# stm32-d40.net
KiCad netlist of a schematic drawn in EAGLE
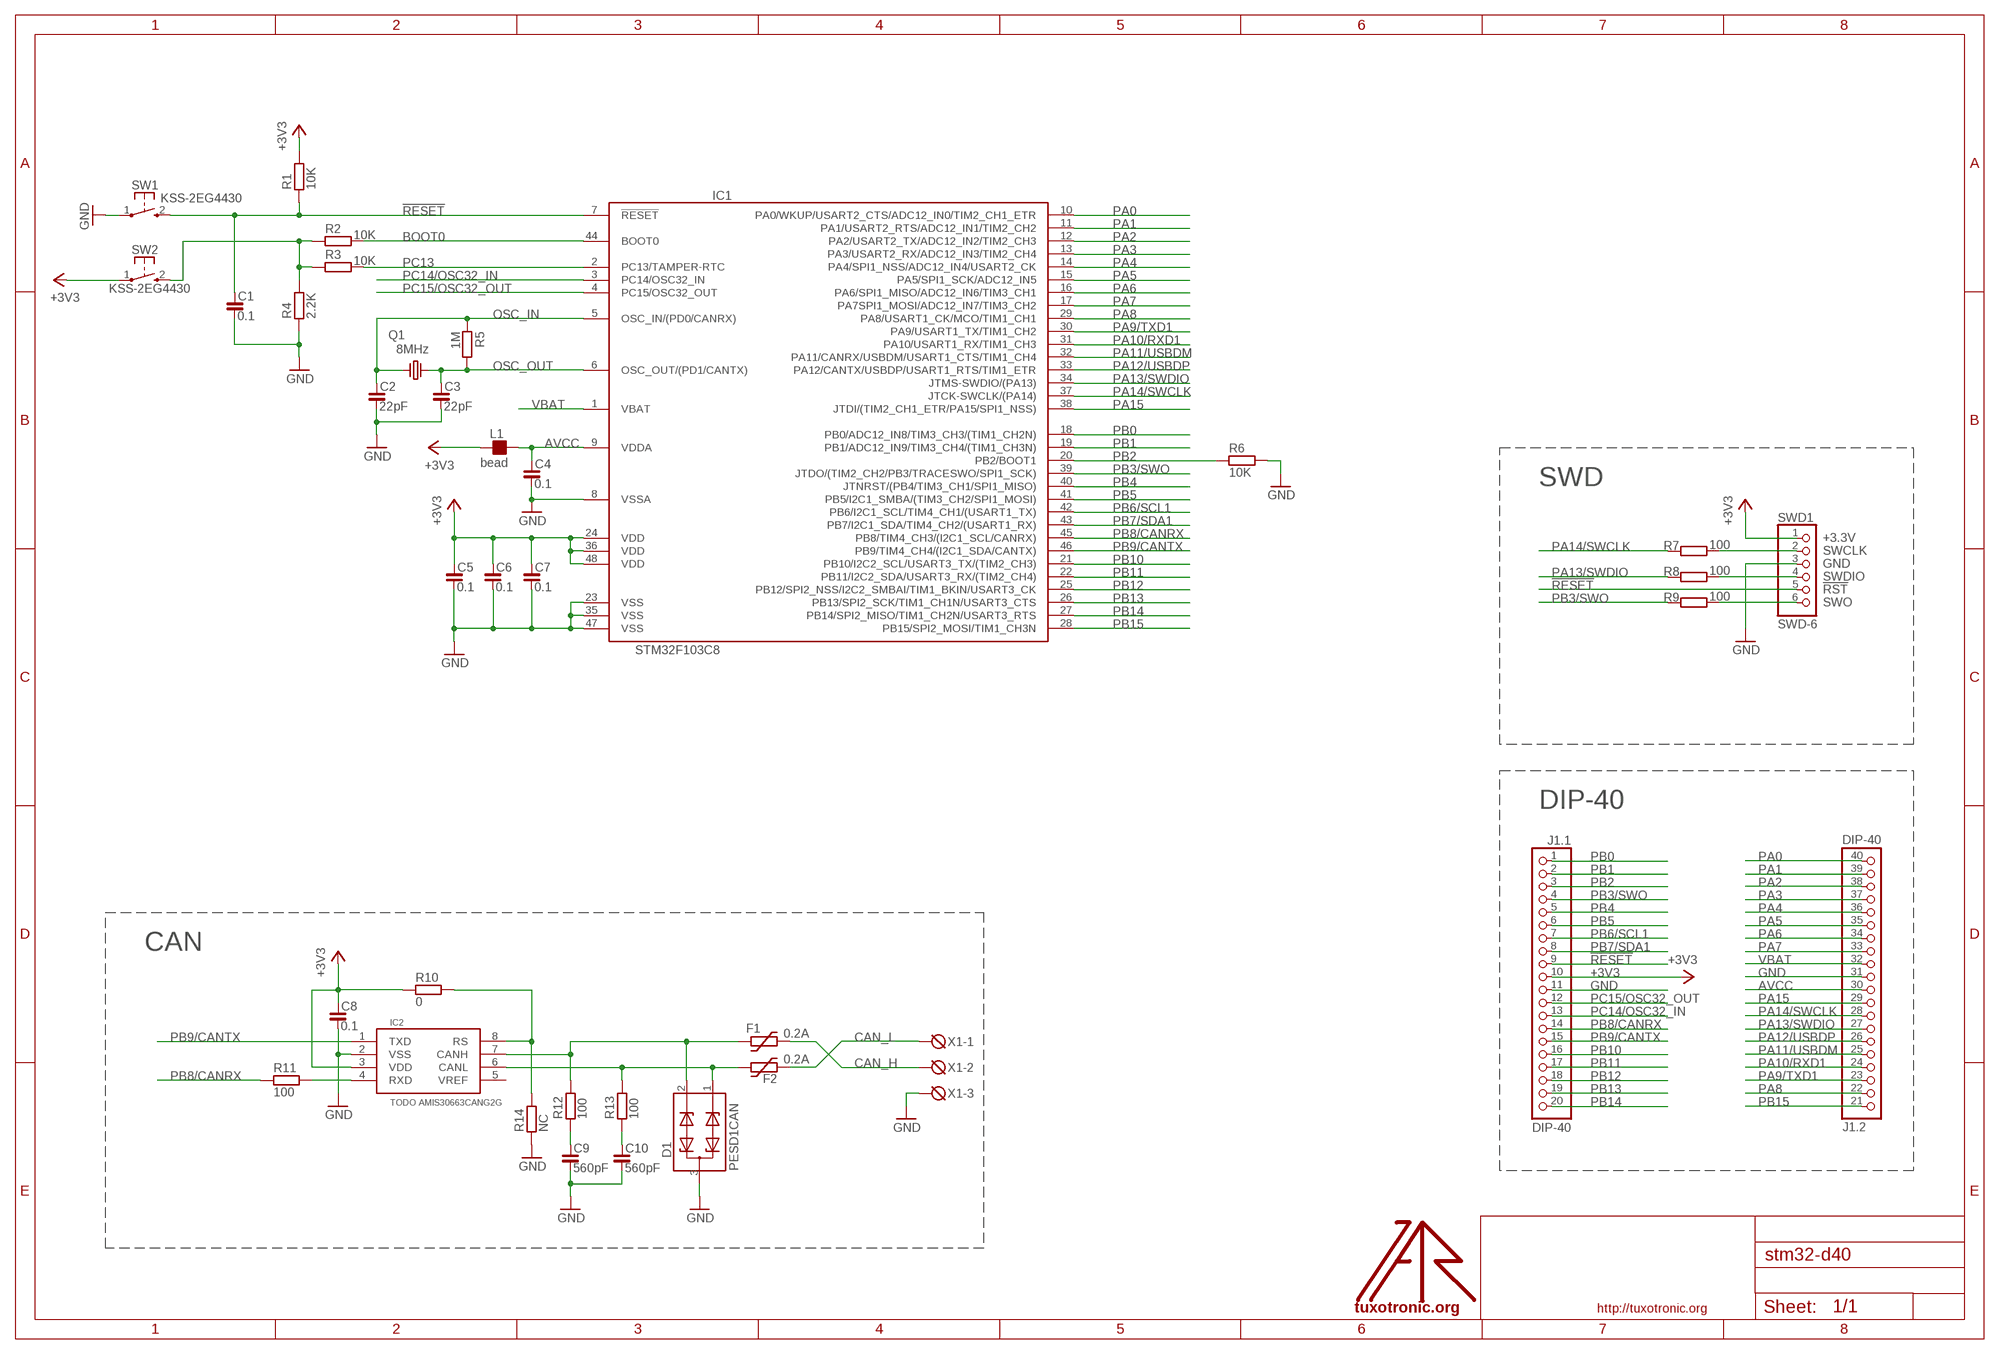
[diagram p0: schematic, sheet 1]

(export (version "E")
  (design (tool "Eeschema 10.0.6"))
  (components
    (comp (ref "C1")
      (value "0.1")
      (footprint "eagle-import:C0603")
      (libsource (lib "eagle-import") (part "C_0603"))
    )
    (comp (ref "C2")
      (value "22pF")
      (footprint "eagle-import:C0603")
      (libsource (lib "eagle-import") (part "C_0603"))
    )
    (comp (ref "C3")
      (value "22pF")
      (footprint "eagle-import:C0603")
      (libsource (lib "eagle-import") (part "C_0603"))
    )
    (comp (ref "C4")
      (value "0.1")
      (footprint "eagle-import:C0603")
      (libsource (lib "eagle-import") (part "C_0603"))
    )
    (comp (ref "C5")
      (value "0.1")
      (footprint "eagle-import:C0603")
      (libsource (lib "eagle-import") (part "C_0603"))
    )
    (comp (ref "C6")
      (value "0.1")
      (footprint "eagle-import:C0603")
      (libsource (lib "eagle-import") (part "C_0603"))
    )
    (comp (ref "C7")
      (value "0.1")
      (footprint "eagle-import:C0603")
      (libsource (lib "eagle-import") (part "C_0603"))
    )
    (comp (ref "C8")
      (value "0.1")
      (footprint "eagle-import:C0603")
      (libsource (lib "eagle-import") (part "C_0603"))
    )
    (comp (ref "C9")
      (value "560pF")
      (footprint "eagle-import:C0603")
      (libsource (lib "eagle-import") (part "C_0603"))
    )
    (comp (ref "C10")
      (value "560pF")
      (footprint "eagle-import:C0603")
      (libsource (lib "eagle-import") (part "C_0603"))
    )
    (comp (ref "D1")
      (value "PESD1CAN")
      (footprint "eagle-import:SOT23")
      (libsource (lib "eagle-import") (part "PESD1CAN"))
    )
    (comp (ref "F1")
      (value "0.2A")
      (footprint "eagle-import:1206L")
      (libsource (lib "eagle-import") (part "1206L"))
    )
    (comp (ref "F2")
      (value "0.2A")
      (footprint "eagle-import:1206L")
      (libsource (lib "eagle-import") (part "1206L"))
    )
    (comp (ref "IC1")
      (value "STM32F103C8")
      (footprint "eagle-import:LQFP48")
      (libsource (lib "eagle-import") (part "STM32F103C8"))
    )
    (comp (ref "IC2")
      (value "TODO AMIS30663CANG2G")
      (footprint "eagle-import:SO08")
      (libsource (lib "eagle-import") (part "SN65HVD230"))
    )
    (comp (ref "J1")
      (value "DIP-40")
      (footprint "eagle-import:DIP-40")
      (libsource (lib "eagle-import") (part "DIP-40"))
    )
    (comp (ref "L1")
      (value "bead")
      (footprint "eagle-import:L0603")
      (libsource (lib "eagle-import") (part "FB_0603"))
    )
    (comp (ref "Q1")
      (value "8MHz")
      (footprint "eagle-import:HC49_S")
      (libsource (lib "eagle-import") (part "CRYSTAL-HC49S"))
    )
    (comp (ref "R1")
      (value "10K")
      (footprint "eagle-import:R0603")
      (libsource (lib "eagle-import") (part "R_0603"))
    )
    (comp (ref "R2")
      (value "10K")
      (footprint "eagle-import:R0603")
      (libsource (lib "eagle-import") (part "R_0603"))
    )
    (comp (ref "R3")
      (value "10K")
      (footprint "eagle-import:R0603")
      (libsource (lib "eagle-import") (part "R_0603"))
    )
    (comp (ref "R4")
      (value "2.2K")
      (footprint "eagle-import:R0603")
      (libsource (lib "eagle-import") (part "R_0603"))
    )
    (comp (ref "R5")
      (value "1M")
      (footprint "eagle-import:R0603")
      (libsource (lib "eagle-import") (part "R_0603"))
    )
    (comp (ref "R6")
      (value "10K")
      (footprint "eagle-import:R0603")
      (libsource (lib "eagle-import") (part "R_0603"))
    )
    (comp (ref "R7")
      (value "100")
      (footprint "eagle-import:R0603")
      (libsource (lib "eagle-import") (part "R_0603"))
    )
    (comp (ref "R8")
      (value "100")
      (footprint "eagle-import:R0603")
      (libsource (lib "eagle-import") (part "R_0603"))
    )
    (comp (ref "R9")
      (value "100")
      (footprint "eagle-import:R0603")
      (libsource (lib "eagle-import") (part "R_0603"))
    )
    (comp (ref "R10")
      (value "0")
      (footprint "eagle-import:R0603")
      (libsource (lib "eagle-import") (part "R_0603"))
    )
    (comp (ref "R11")
      (value "100")
      (footprint "eagle-import:R0603")
      (libsource (lib "eagle-import") (part "R_0603"))
    )
    (comp (ref "R12")
      (value "100")
      (footprint "eagle-import:R0603")
      (libsource (lib "eagle-import") (part "R_0603"))
    )
    (comp (ref "R13")
      (value "100")
      (footprint "eagle-import:R0603")
      (libsource (lib "eagle-import") (part "R_0603"))
    )
    (comp (ref "R14")
      (value "NC")
      (footprint "eagle-import:R0603")
      (libsource (lib "eagle-import") (part "R_0603"))
    )
    (comp (ref "SW1")
      (value "KSS-2EG4430")
      (footprint "eagle-import:KSS-2EG4430")
      (libsource (lib "eagle-import") (part "KSS-2EG4430"))
    )
    (comp (ref "SW2")
      (value "KSS-2EG4430")
      (footprint "eagle-import:KSS-2EG4430")
      (libsource (lib "eagle-import") (part "KSS-2EG4430"))
    )
    (comp (ref "SWD1")
      (value "SWD-6")
      (footprint "eagle-import:JTAG6PIN")
      (libsource (lib "eagle-import") (part "SWD-6"))
    )
    (comp (ref "U$")
      (value "LOGO")
      (footprint "eagle-import:TT_LOGO")
      (libsource (lib "eagle-import") (part "LOGO"))
    )
    (comp (ref "X1")
      (value "DG3XX-03-3.5")
      (footprint "eagle-import:DG350-3.5-03P")
      (libsource (lib "eagle-import") (part "DG3XX-03-3.5"))
    )
  )
  (nets
    (net (code "1") (name "+3V3") (class "Default")
      (node (ref "C5") (pin "1") (pinfunction "1_1") (pintype "passive"))
      (node (ref "C6") (pin "1") (pinfunction "1_1") (pintype "passive"))
      (node (ref "C7") (pin "1") (pinfunction "1_1") (pintype "passive"))
      (node (ref "C8") (pin "1") (pinfunction "1_1") (pintype "passive"))
      (node (ref "IC1") (pin "24") (pinfunction "VDD_24") (pintype "power_in"))
      (node (ref "IC1") (pin "36") (pinfunction "VDD_36") (pintype "power_in"))
      (node (ref "IC1") (pin "48") (pinfunction "VDD_48") (pintype "power_in"))
      (node (ref "IC2") (pin "3") (pinfunction "VDD_3") (pintype "power_in"))
      (node (ref "J1") (pin "10") (pinfunction "10_10") (pintype "passive"))
      (node (ref "L1") (pin "1") (pinfunction "1_1") (pintype "passive"))
      (node (ref "R1") (pin "2") (pinfunction "2_2") (pintype "passive"))
      (node (ref "R10") (pin "1") (pinfunction "1_1") (pintype "passive"))
      (node (ref "SW2") (pin "1") (pinfunction "P_1") (pintype "passive"))
      (node (ref "SWD1") (pin "1") (pinfunction "1_1") (pintype "passive"))
    )
    (net (code "2") (name "/AVCC") (class "Default")
      (node (ref "C4") (pin "1") (pinfunction "1_1") (pintype "passive"))
      (node (ref "IC1") (pin "9") (pinfunction "VDDA_9") (pintype "power_in"))
      (node (ref "J1") (pin "30") (pinfunction "10_30") (pintype "passive"))
      (node (ref "L1") (pin "2") (pinfunction "2_2") (pintype "passive"))
    )
    (net (code "3") (name "/BOOT0") (class "Default")
      (node (ref "IC1") (pin "44") (pinfunction "BOOT0_44") (pintype "input"))
      (node (ref "R2") (pin "2") (pinfunction "2_2") (pintype "passive"))
    )
    (net (code "4") (name "/CAN_H") (class "Default")
      (node (ref "F1") (pin "P$2") (pinfunction "2_P$2") (pintype "passive"))
      (node (ref "X1") (pin "2") (pinfunction "KL_2") (pintype "passive"))
    )
    (net (code "5") (name "/CAN_L") (class "Default")
      (node (ref "F2") (pin "P$2") (pinfunction "2_P$2") (pintype "passive"))
      (node (ref "X1") (pin "1") (pinfunction "KL_1") (pintype "passive"))
    )
    (net (code "6") (name "/OSC_IN") (class "Default")
      (node (ref "C2") (pin "1") (pinfunction "1_1") (pintype "passive"))
      (node (ref "IC1") (pin "5") (pinfunction "OSC_IN/(PD0/CANRX)_5") (pintype "input"))
      (node (ref "Q1") (pin "1") (pinfunction "1_1") (pintype "passive"))
      (node (ref "R5") (pin "1") (pinfunction "1_1") (pintype "passive"))
    )
    (net (code "7") (name "/OSC_OUT") (class "Default")
      (node (ref "C3") (pin "1") (pinfunction "1_1") (pintype "passive"))
      (node (ref "IC1") (pin "6") (pinfunction "OSC_OUT/(PD1/CANTX)_6") (pintype "output"))
      (node (ref "Q1") (pin "2") (pinfunction "2_2") (pintype "passive"))
      (node (ref "R5") (pin "2") (pinfunction "2_2") (pintype "passive"))
    )
    (net (code "8") (name "/PA0") (class "Default")
      (node (ref "IC1") (pin "10") (pinfunction "PA0/WKUP/USART2_CTS/ADC12_IN0/TIM2_CH1_ETR_10") (pintype "bidirectional"))
      (node (ref "J1") (pin "40") (pinfunction "20_40") (pintype "passive"))
    )
    (net (code "9") (name "/PA1") (class "Default")
      (node (ref "IC1") (pin "11") (pinfunction "PA1/USART2_RTS/ADC12_IN1/TIM2_CH2_11") (pintype "bidirectional"))
      (node (ref "J1") (pin "39") (pinfunction "19_39") (pintype "passive"))
    )
    (net (code "10") (name "/PA2") (class "Default")
      (node (ref "IC1") (pin "12") (pinfunction "PA2/USART2_TX/ADC12_IN2/TIM2_CH3_12") (pintype "bidirectional"))
      (node (ref "J1") (pin "38") (pinfunction "18_38") (pintype "passive"))
    )
    (net (code "11") (name "/PA3") (class "Default")
      (node (ref "IC1") (pin "13") (pinfunction "PA3/USART2_RX/ADC12_IN3/TIM2_CH4_13") (pintype "bidirectional"))
      (node (ref "J1") (pin "37") (pinfunction "17_37") (pintype "passive"))
    )
    (net (code "12") (name "/PA4") (class "Default")
      (node (ref "IC1") (pin "14") (pinfunction "PA4/SPI1_NSS/ADC12_IN4/USART2_CK_14") (pintype "bidirectional"))
      (node (ref "J1") (pin "36") (pinfunction "16_36") (pintype "passive"))
    )
    (net (code "13") (name "/PA5") (class "Default")
      (node (ref "IC1") (pin "15") (pinfunction "PA5/SPI1_SCK/ADC12_IN5_15") (pintype "bidirectional"))
      (node (ref "J1") (pin "35") (pinfunction "15_35") (pintype "passive"))
    )
    (net (code "14") (name "/PA6") (class "Default")
      (node (ref "IC1") (pin "16") (pinfunction "PA6/SPI1_MISO/ADC12_IN6/TIM3_CH1_16") (pintype "bidirectional"))
      (node (ref "J1") (pin "34") (pinfunction "14_34") (pintype "passive"))
    )
    (net (code "15") (name "/PA7") (class "Default")
      (node (ref "IC1") (pin "17") (pinfunction "PA7SPI1_MOSI/ADC12_IN7/TIM3_CH2_17") (pintype "bidirectional"))
      (node (ref "J1") (pin "33") (pinfunction "13_33") (pintype "passive"))
    )
    (net (code "16") (name "/PA8") (class "Default")
      (node (ref "IC1") (pin "29") (pinfunction "PA8/USART1_CK/MCO/TIM1_CH1_29") (pintype "bidirectional"))
      (node (ref "J1") (pin "22") (pinfunction "2_22") (pintype "passive"))
    )
    (net (code "17") (name "/PA9{slash}TXD1") (class "Default")
      (node (ref "IC1") (pin "30") (pinfunction "PA9/USART1_TX/TIM1_CH2_30") (pintype "bidirectional"))
      (node (ref "J1") (pin "23") (pinfunction "3_23") (pintype "passive"))
    )
    (net (code "18") (name "/PA10{slash}RXD1") (class "Default")
      (node (ref "IC1") (pin "31") (pinfunction "PA10/USART1_RX/TIM1_CH3_31") (pintype "bidirectional"))
      (node (ref "J1") (pin "24") (pinfunction "4_24") (pintype "passive"))
    )
    (net (code "19") (name "/PA11{slash}USBDM") (class "Default")
      (node (ref "IC1") (pin "32") (pinfunction "PA11/CANRX/USBDM/USART1_CTS/TIM1_CH4_32") (pintype "bidirectional"))
      (node (ref "J1") (pin "25") (pinfunction "5_25") (pintype "passive"))
    )
    (net (code "20") (name "/PA12{slash}USBDP") (class "Default")
      (node (ref "IC1") (pin "33") (pinfunction "PA12/CANTX/USBDP/USART1_RTS/TIM1_ETR_33") (pintype "bidirectional"))
      (node (ref "J1") (pin "26") (pinfunction "6_26") (pintype "passive"))
    )
    (net (code "21") (name "/PA13{slash}SWDIO") (class "Default")
      (node (ref "IC1") (pin "34") (pinfunction "JTMS-SWDIO/(PA13)_34") (pintype "bidirectional"))
      (node (ref "J1") (pin "27") (pinfunction "7_27") (pintype "passive"))
      (node (ref "R8") (pin "1") (pinfunction "1_1") (pintype "passive"))
    )
    (net (code "22") (name "/PA14{slash}SWCLK") (class "Default")
      (node (ref "IC1") (pin "37") (pinfunction "JTCK-SWCLK/(PA14)_37") (pintype "bidirectional"))
      (node (ref "J1") (pin "28") (pinfunction "8_28") (pintype "passive"))
      (node (ref "R7") (pin "1") (pinfunction "1_1") (pintype "passive"))
    )
    (net (code "23") (name "/PA15") (class "Default")
      (node (ref "IC1") (pin "38") (pinfunction "JTDI/(TIM2_CH1_ETR/PA15/SPI1_NSS)_38") (pintype "bidirectional"))
      (node (ref "J1") (pin "29") (pinfunction "9_29") (pintype "passive"))
    )
    (net (code "24") (name "/PB0") (class "Default")
      (node (ref "IC1") (pin "18") (pinfunction "PB0/ADC12_IN8/TIM3_CH3/(TIM1_CH2N)_18") (pintype "bidirectional"))
      (node (ref "J1") (pin "1") (pinfunction "1_1") (pintype "passive"))
    )
    (net (code "25") (name "/PB1") (class "Default")
      (node (ref "IC1") (pin "19") (pinfunction "PB1/ADC12_IN9/TIM3_CH4/(TIM1_CH3N)_19") (pintype "bidirectional"))
      (node (ref "J1") (pin "2") (pinfunction "2_2") (pintype "passive"))
    )
    (net (code "26") (name "/PB2") (class "Default")
      (node (ref "IC1") (pin "20") (pinfunction "PB2/BOOT1_20") (pintype "bidirectional"))
      (node (ref "J1") (pin "3") (pinfunction "3_3") (pintype "passive"))
      (node (ref "R6") (pin "1") (pinfunction "1_1") (pintype "passive"))
    )
    (net (code "27") (name "/PB3{slash}SWO") (class "Default")
      (node (ref "IC1") (pin "39") (pinfunction "JTDO/(TIM2_CH2/PB3/TRACESWO/SPI1_SCK)_39") (pintype "bidirectional"))
      (node (ref "J1") (pin "4") (pinfunction "4_4") (pintype "passive"))
      (node (ref "R9") (pin "1") (pinfunction "1_1") (pintype "passive"))
    )
    (net (code "28") (name "/PB4") (class "Default")
      (node (ref "IC1") (pin "40") (pinfunction "JTNRST/(PB4/TIM3_CH1/SPI1_MISO)_40") (pintype "bidirectional"))
      (node (ref "J1") (pin "5") (pinfunction "5_5") (pintype "passive"))
    )
    (net (code "29") (name "/PB5") (class "Default")
      (node (ref "IC1") (pin "41") (pinfunction "PB5/I2C1_SMBA/(TIM3_CH2/SPI1_MOSI)_41") (pintype "bidirectional"))
      (node (ref "J1") (pin "6") (pinfunction "6_6") (pintype "passive"))
    )
    (net (code "30") (name "/PB6{slash}SCL1") (class "Default")
      (node (ref "IC1") (pin "42") (pinfunction "PB6/I2C1_SCL/TIM4_CH1/(USART1_TX)_42") (pintype "bidirectional"))
      (node (ref "J1") (pin "7") (pinfunction "7_7") (pintype "passive"))
    )
    (net (code "31") (name "/PB7{slash}SDA1") (class "Default")
      (node (ref "IC1") (pin "43") (pinfunction "PB7/I2C1_SDA/TIM4_CH2/(USART1_RX)_43") (pintype "bidirectional"))
      (node (ref "J1") (pin "8") (pinfunction "8_8") (pintype "passive"))
    )
    (net (code "32") (name "/PB8{slash}CANRX") (class "Default")
      (node (ref "IC1") (pin "45") (pinfunction "PB8/TIM4_CH3/(I2C1_SCL/CANRX)_45") (pintype "bidirectional"))
      (node (ref "J1") (pin "14") (pinfunction "14_14") (pintype "passive"))
      (node (ref "R11") (pin "1") (pinfunction "1_1") (pintype "passive"))
    )
    (net (code "33") (name "/PB9{slash}CANTX") (class "Default")
      (node (ref "IC1") (pin "46") (pinfunction "PB9/TIM4_CH4/(I2C1_SDA/CANTX)_46") (pintype "bidirectional"))
      (node (ref "IC2") (pin "1") (pinfunction "TXD_1") (pintype "input"))
      (node (ref "J1") (pin "15") (pinfunction "15_15") (pintype "passive"))
    )
    (net (code "34") (name "/PB10") (class "Default")
      (node (ref "IC1") (pin "21") (pinfunction "PB10/I2C2_SCL/USART3_TX/(TIM2_CH3)_21") (pintype "bidirectional"))
      (node (ref "J1") (pin "16") (pinfunction "16_16") (pintype "passive"))
    )
    (net (code "35") (name "/PB11") (class "Default")
      (node (ref "IC1") (pin "22") (pinfunction "PB11/I2C2_SDA/USART3_RX/(TIM2_CH4)_22") (pintype "bidirectional"))
      (node (ref "J1") (pin "17") (pinfunction "17_17") (pintype "passive"))
    )
    (net (code "36") (name "/PB12") (class "Default")
      (node (ref "IC1") (pin "25") (pinfunction "PB12/SPI2_NSS/I2C2_SMBAI/TIM1_BKIN/USART3_CK_25") (pintype "bidirectional"))
      (node (ref "J1") (pin "18") (pinfunction "18_18") (pintype "passive"))
    )
    (net (code "37") (name "/PB13") (class "Default")
      (node (ref "IC1") (pin "26") (pinfunction "PB13/SPI2_SCK/TIM1_CH1N/USART3_CTS_26") (pintype "bidirectional"))
      (node (ref "J1") (pin "19") (pinfunction "19_19") (pintype "passive"))
    )
    (net (code "38") (name "/PB14") (class "Default")
      (node (ref "IC1") (pin "27") (pinfunction "PB14/SPI2_MISO/TIM1_CH2N/USART3_RTS_27") (pintype "bidirectional"))
      (node (ref "J1") (pin "20") (pinfunction "20_20") (pintype "passive"))
    )
    (net (code "39") (name "/PB15") (class "Default")
      (node (ref "IC1") (pin "28") (pinfunction "PB15/SPI2_MOSI/TIM1_CH3N_28") (pintype "bidirectional"))
      (node (ref "J1") (pin "21") (pinfunction "1_21") (pintype "passive"))
    )
    (net (code "40") (name "/PC13") (class "Default")
      (node (ref "IC1") (pin "2") (pinfunction "PC13/TAMPER-RTC_2") (pintype "bidirectional"))
      (node (ref "R3") (pin "2") (pinfunction "2_2") (pintype "passive"))
    )
    (net (code "41") (name "/PC14{slash}OSC32_IN") (class "Default")
      (node (ref "IC1") (pin "3") (pinfunction "PC14/OSC32_IN_3") (pintype "bidirectional"))
      (node (ref "J1") (pin "13") (pinfunction "13_13") (pintype "passive"))
    )
    (net (code "42") (name "/PC15{slash}OSC32_OUT") (class "Default")
      (node (ref "IC1") (pin "4") (pinfunction "PC15/OSC32_OUT_4") (pintype "bidirectional"))
      (node (ref "J1") (pin "12") (pinfunction "12_12") (pintype "passive"))
    )
    (net (code "43") (name "/VBAT") (class "Default")
      (node (ref "IC1") (pin "1") (pinfunction "VBAT_1") (pintype "power_in"))
      (node (ref "J1") (pin "32") (pinfunction "12_32") (pintype "passive"))
    )
    (net (code "44") (name "/~{RESET}") (class "Default")
      (node (ref "C1") (pin "1") (pinfunction "1_1") (pintype "passive"))
      (node (ref "IC1") (pin "7") (pinfunction "~{RESET}_7") (pintype "input"))
      (node (ref "J1") (pin "9") (pinfunction "9_9") (pintype "passive"))
      (node (ref "R1") (pin "1") (pinfunction "1_1") (pintype "passive"))
      (node (ref "SW1") (pin "2") (pinfunction "S_2") (pintype "passive"))
      (node (ref "SWD1") (pin "5") (pinfunction "5_5") (pintype "passive"))
    )
    (net (code "45") (name "GND") (class "Default")
      (node (ref "C1") (pin "2") (pinfunction "2_2") (pintype "passive"))
      (node (ref "C10") (pin "2") (pinfunction "2_2") (pintype "passive"))
      (node (ref "C2") (pin "2") (pinfunction "2_2") (pintype "passive"))
      (node (ref "C3") (pin "2") (pinfunction "2_2") (pintype "passive"))
      (node (ref "C4") (pin "2") (pinfunction "2_2") (pintype "passive"))
      (node (ref "C5") (pin "2") (pinfunction "2_2") (pintype "passive"))
      (node (ref "C6") (pin "2") (pinfunction "2_2") (pintype "passive"))
      (node (ref "C7") (pin "2") (pinfunction "2_2") (pintype "passive"))
      (node (ref "C8") (pin "2") (pinfunction "2_2") (pintype "passive"))
      (node (ref "C9") (pin "2") (pinfunction "2_2") (pintype "passive"))
      (node (ref "D1") (pin "3") (pinfunction "3_3") (pintype "passive"))
      (node (ref "IC1") (pin "23") (pinfunction "VSS_23") (pintype "power_in"))
      (node (ref "IC1") (pin "35") (pinfunction "VSS_35") (pintype "power_in"))
      (node (ref "IC1") (pin "47") (pinfunction "VSS_47") (pintype "power_in"))
      (node (ref "IC1") (pin "8") (pinfunction "VSSA_8") (pintype "power_in"))
      (node (ref "IC2") (pin "2") (pinfunction "VSS_2") (pintype "power_in"))
      (node (ref "J1") (pin "11") (pinfunction "11_11") (pintype "passive"))
      (node (ref "J1") (pin "31") (pinfunction "11_31") (pintype "passive"))
      (node (ref "R14") (pin "1") (pinfunction "1_1") (pintype "passive"))
      (node (ref "R4") (pin "1") (pinfunction "1_1") (pintype "passive"))
      (node (ref "R6") (pin "2") (pinfunction "2_2") (pintype "passive"))
      (node (ref "SW1") (pin "1") (pinfunction "P_1") (pintype "passive"))
      (node (ref "SWD1") (pin "3") (pinfunction "3_3") (pintype "passive"))
      (node (ref "X1") (pin "3") (pinfunction "KL_3") (pintype "passive"))
    )
    (net (code "46") (name "Net-(C9-Pad1)") (class "Default")
      (node (ref "C9") (pin "1") (pinfunction "1_1") (pintype "passive"))
      (node (ref "R12") (pin "1") (pinfunction "1_1") (pintype "passive"))
    )
    (net (code "47") (name "Net-(C10-Pad1)") (class "Default")
      (node (ref "C10") (pin "1") (pinfunction "1_1") (pintype "passive"))
      (node (ref "R13") (pin "1") (pinfunction "1_1") (pintype "passive"))
    )
    (net (code "48") (name "Net-(F1-1)") (class "Default")
      (node (ref "D1") (pin "2") (pinfunction "2_2") (pintype "passive"))
      (node (ref "F1") (pin "P$1") (pinfunction "1_P$1") (pintype "passive"))
      (node (ref "IC2") (pin "7") (pinfunction "CANH_7") (pintype "bidirectional"))
      (node (ref "R12") (pin "2") (pinfunction "2_2") (pintype "passive"))
    )
    (net (code "49") (name "Net-(F2-1)") (class "Default")
      (node (ref "D1") (pin "1") (pinfunction "1_1") (pintype "passive"))
      (node (ref "F2") (pin "P$1") (pinfunction "1_P$1") (pintype "passive"))
      (node (ref "IC2") (pin "6") (pinfunction "CANL_6") (pintype "bidirectional"))
      (node (ref "R13") (pin "2") (pinfunction "2_2") (pintype "passive"))
    )
    (net (code "50") (name "Net-(IC2-RS)") (class "Default")
      (node (ref "IC2") (pin "8") (pinfunction "RS_8") (pintype "input"))
      (node (ref "R10") (pin "2") (pinfunction "2_2") (pintype "passive"))
      (node (ref "R14") (pin "2") (pinfunction "2_2") (pintype "passive"))
    )
    (net (code "51") (name "Net-(IC2-RXD)") (class "Default")
      (node (ref "IC2") (pin "4") (pinfunction "RXD_4") (pintype "output"))
      (node (ref "R11") (pin "2") (pinfunction "2_2") (pintype "passive"))
    )
    (net (code "52") (name "Net-(R7-Pad2)") (class "Default")
      (node (ref "R7") (pin "2") (pinfunction "2_2") (pintype "passive"))
      (node (ref "SWD1") (pin "2") (pinfunction "2_2") (pintype "passive"))
    )
    (net (code "53") (name "Net-(R8-Pad2)") (class "Default")
      (node (ref "R8") (pin "2") (pinfunction "2_2") (pintype "passive"))
      (node (ref "SWD1") (pin "4") (pinfunction "4_4") (pintype "passive"))
    )
    (net (code "54") (name "Net-(R9-Pad2)") (class "Default")
      (node (ref "R9") (pin "2") (pinfunction "2_2") (pintype "passive"))
      (node (ref "SWD1") (pin "6") (pinfunction "6_6") (pintype "passive"))
    )
    (net (code "55") (name "Net-(SW2-S)") (class "Default")
      (node (ref "R2") (pin "1") (pinfunction "1_1") (pintype "passive"))
      (node (ref "R3") (pin "1") (pinfunction "1_1") (pintype "passive"))
      (node (ref "R4") (pin "2") (pinfunction "2_2") (pintype "passive"))
      (node (ref "SW2") (pin "2") (pinfunction "S_2") (pintype "passive"))
    )
    (net (code "56") (name "unconnected-(IC2-VREF-Pad5)") (class "Default")
      (node (ref "IC2") (pin "5") (pinfunction "VREF_5") (pintype "passive"))
    )
  )
)
